# 105848.net
KiCad netlist of a schematic drawn in Altium Designer
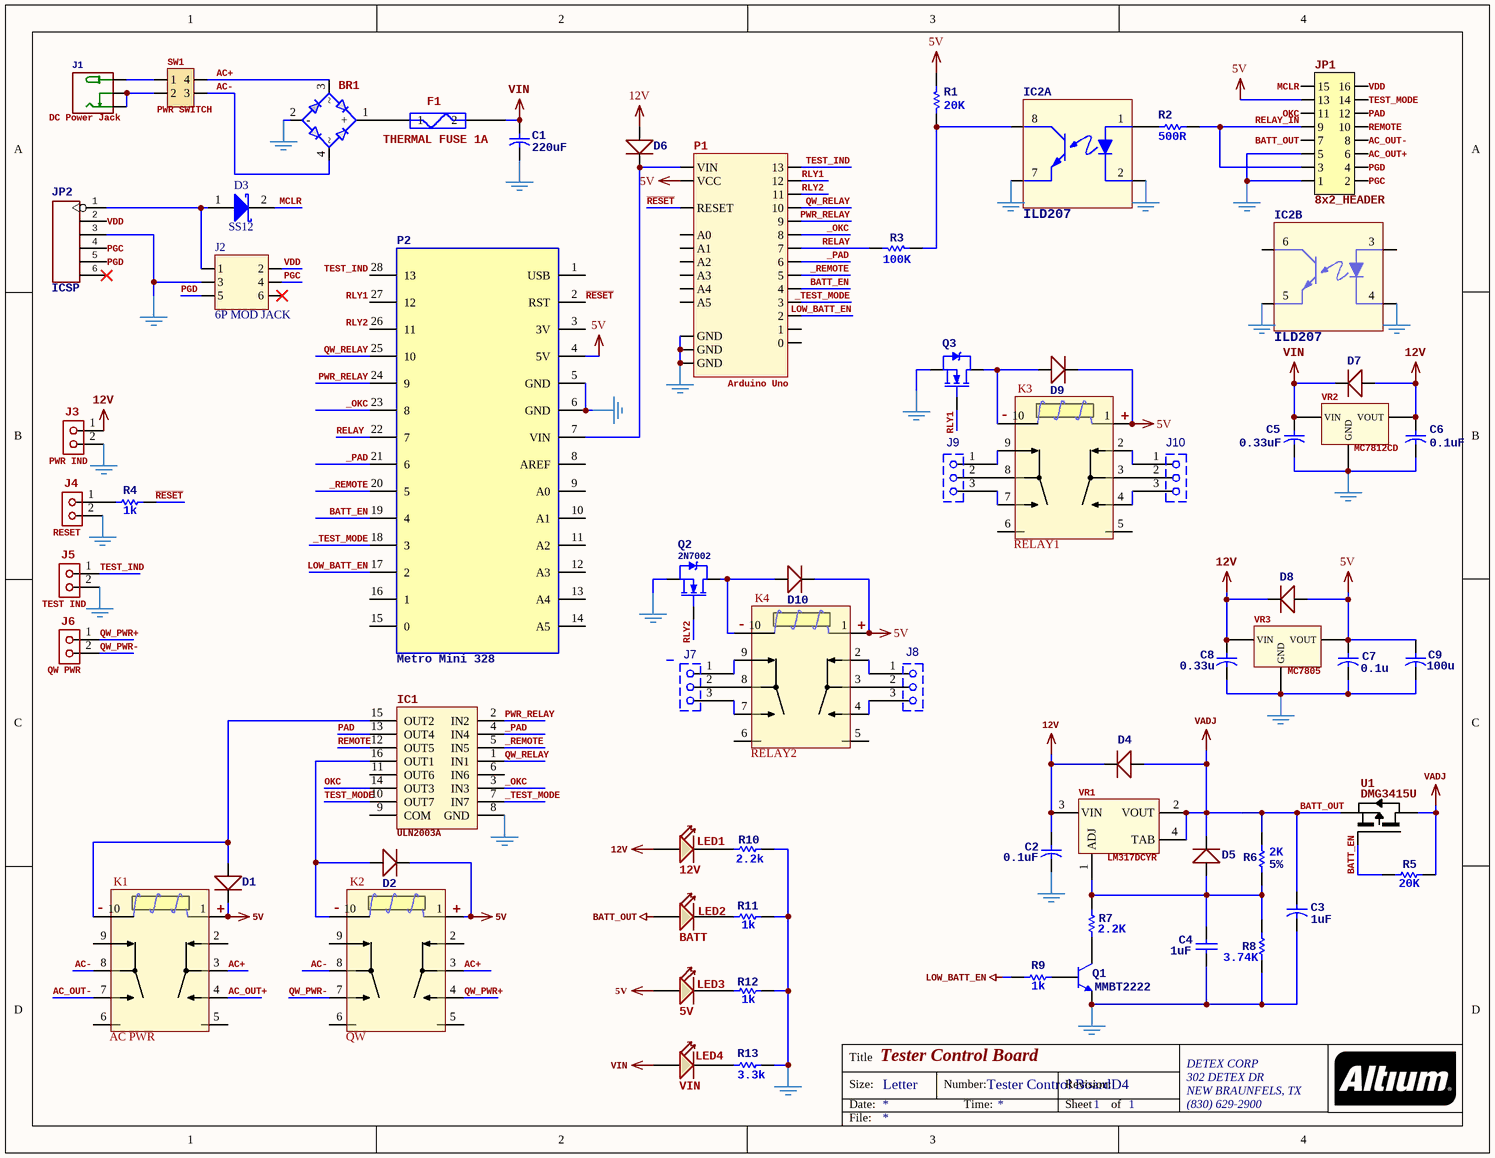
[diagram p0: 105848.SchDoc]

(export (version "E")
  (design (tool "Eeschema 10.0.6"))
  (components
    (comp (ref "BR1")
      (value "BRIDGE - SMT")
      (footprint "BRIDGE_1A_SMT")
      (description "1A SMT Bridge Rectifier")
      (libsource (lib "AltiumIntegratedLibrary") (part "BRIDGE_1A_SMT"))
    )
    (comp (ref "C1")
      (value "220uF")
      (footprint "CAPR5-4X5")
      (description "Capacitor TO - 200 SPACING")
      (fields (field (name "Comment") "Capacitor - Thru-Hole"))
      (libsource (lib "Train2") (part "CAP200"))
    )
    (comp (ref "C2")
      (value "0.1uF")
      (footprint "CAPC1206(3216)110_M")
      (description "1206 Ceramic Capacitor")
      (fields (field (name "Comment") "1206 Capacitor"))
      (libsource (lib "Train2") (part "CAP200"))
    )
    (comp (ref "C3")
      (value "1uF")
      (footprint "CAPC1206(3216)110_M")
      (description "1206 Ceramic Capacitor")
      (fields (field (name "Comment") "1206 Capacitor"))
      (libsource (lib "Train2") (part "CAP200"))
    )
    (comp (ref "C4")
      (value "1uF")
      (footprint "CAPC1206(3216)110_M")
      (description "1206 Ceramic Capacitor")
      (fields (field (name "Comment") "1206 Capacitor"))
      (libsource (lib "Miscellaneous Devices") (part "Cap"))
    )
    (comp (ref "C5")
      (value "0.33uF")
      (footprint "RESC1206(3216)_M")
      (description "1206 Ceramic Capacitor")
      (fields (field (name "Comment") "1206 Capacitor"))
      (libsource (lib "Train2") (part "CAP200"))
    )
    (comp (ref "C6")
      (value "0.1uF")
      (footprint "RESC1206(3216)_M")
      (description "1206 Ceramic Capacitor")
      (fields (field (name "Comment") "1206 Capacitor"))
      (libsource (lib "") (part "CAP200_1"))
    )
    (comp (ref "C7")
      (value "0.1u")
      (footprint "RESC1206(3216)_M")
      (description "1206 Ceramic Capacitor")
      (fields (field (name "Comment") "1206 Capacitor"))
      (libsource (lib "") (part "CAP200_1"))
    )
    (comp (ref "C8")
      (value "0.33u")
      (footprint "RESC1206(3216)_M")
      (description "1206 Ceramic Capacitor")
      (fields (field (name "Comment") "1206 Capacitor"))
      (libsource (lib "") (part "CAP200_1"))
    )
    (comp (ref "C9")
      (value "100u")
      (footprint "CAPR5-4X5")
      (description "Capacitor TO - 200 SPACING")
      (fields (field (name "Comment") "Capacitor - Thru-Hole"))
      (libsource (lib "Train2") (part "CAP200"))
    )
    (comp (ref "D1")
      (value "BAS20")
      (footprint "SOT-23_M")
      (fields (field (name "MPN") "B5819W"))
      (libsource (lib "Seeed-Diode-2016") (part "SMD-DIODE-SCHOTTKY-20V-1A(SOD-123)"))
    )
    (comp (ref "D2")
      (value "BAS20")
      (footprint "SOT-23_M")
      (fields (field (name "MPN") "B5819W"))
      (libsource (lib "Seeed-Diode-2016") (part "SMD-DIODE-SCHOTTKY-20V-1A(SOD-123)"))
    )
    (comp (ref "D3")
      (value "SS12")
      (footprint "SMB_2")
      (description "Schottky Diode, SMD")
      (libsource (lib "Miscellaneous Devices") (part "D Schottky"))
    )
    (comp (ref "D4")
      (value "1N4002")
      (footprint "DO-214AC")
      (description "Diode, SMD")
      (fields (field (name "MPN") "B5819W"))
      (libsource (lib "AltiumIntegratedLibrary") (part "SMD-DIODE-SCHOTTKY-20V-1A(SOD-123)"))
    )
    (comp (ref "D5")
      (value "1N4002")
      (footprint "DO-214AC")
      (description "Diode, SMD")
      (fields (field (name "MPN") "B5819W"))
      (libsource (lib "AltiumIntegratedLibrary") (part "SMD-DIODE-SCHOTTKY-20V-1A(SOD-123)"))
    )
    (comp (ref "D6")
      (value "1N4002")
      (footprint "DO-214AC")
      (description "Diode, SMD")
      (fields (field (name "MPN") "B5819W"))
      (libsource (lib "AltiumIntegratedLibrary") (part "SMD-DIODE-SCHOTTKY-20V-1A(SOD-123)"))
    )
    (comp (ref "D7")
      (value "1N4002")
      (footprint "DO-214AC")
      (description "Diode, SMD")
      (fields (field (name "MPN") "B5819W"))
      (libsource (lib "AltiumIntegratedLibrary") (part "SMD-DIODE-SCHOTTKY-20V-1A(SOD-123)"))
    )
    (comp (ref "D8")
      (value "1N4002")
      (footprint "DO-214AC")
      (description "Diode, SMD")
      (fields (field (name "MPN") "B5819W"))
      (libsource (lib "AltiumIntegratedLibrary") (part "SMD-DIODE-SCHOTTKY-20V-1A(SOD-123)"))
    )
    (comp (ref "D9")
      (value "BAS20")
      (footprint "SOT-23_M")
      (description "Diode, SMD")
      (fields (field (name "MPN") "B5819W"))
      (libsource (lib "AltiumIntegratedLibrary") (part "SMD-DIODE-SCHOTTKY-20V-1A(SOD-123)"))
    )
    (comp (ref "D10")
      (value "BAS20")
      (footprint "SOT-23_M")
      (fields (field (name "MPN") "B5819W"))
      (libsource (lib "AltiumIntegratedLibrary") (part "SMD-DIODE-SCHOTTKY-20V-1A(SOD-123)"))
    )
    (comp (ref "F1")
      (value "THERMAL FUSE 1A")
      (footprint "FUSE_200")
      (description "FUSE_200")
      (libsource (lib "Train2") (part "FUSE_200"))
    )
    (comp (ref "IC1")
      (value "ULN2003A")
      (footprint "SO-16_M")
      (description "ULN2003")
      (libsource (lib "Train2") (part "ULN2003"))
    )
    (comp (ref "IC2")
      (value "ILD207")
      (footprint "SO8_N")
      (description "DUAL OPTO ISOLATOR")
      (fields (field (name "MPN") "ILD207T"))
      (libsource (lib "AltiumIntegratedLibrary") (part "OPTO_DUAL_2"))
    )
    (comp (ref "J1")
      (value "DC Power Jack")
      (footprint "train2:KLD-0202_2")
      (description "DC POWER PLUG")
      (fields (field (name "MPN") "DC-005"))
      (libsource (lib "Seeed-Connector -2016") (part "CONN-POWER-JACK-2.1MM(DC-005)"))
    )
    (comp (ref "J2")
      (value "6P MOD JACK")
      (footprint "TECO-5520470-3_V")
      (description "6 Position Modular Jack Connector")
      (fields (field (name "MANUFACTURER") "Tetco") (field (name "MPN") "TECO-5520470-3_V"))
      (libsource (lib "105848_revD3") (part "Modular Jack 6P"))
    )
    (comp (ref "J3")
      (value "PWR IND")
      (footprint "JMP2")
      (description "JUMPER_2")
      (libsource (lib "105848") (part "JUMPER_2"))
    )
    (comp (ref "J4")
      (value "RESET")
      (footprint "JMP2")
      (description "JUMPER_2")
      (libsource (lib "105848") (part "JUMPER_2"))
    )
    (comp (ref "J5")
      (value "TEST IND")
      (footprint "JMP2")
      (description "JUMPER_2")
      (libsource (lib "105848") (part "JUMPER_2"))
    )
    (comp (ref "J6")
      (value "QW PWR")
      (footprint "JMP2")
      (description "JUMPER_2")
      (libsource (lib "105848") (part "JUMPER_2"))
    )
    (comp (ref "J7")
      (value "JMP_3PIN")
      (footprint "JMP3")
      (libsource (lib "AltiumIntegratedLibrary") (part "JMP_3PIN"))
    )
    (comp (ref "J8")
      (value "JMP_3PIN")
      (footprint "JMP3")
      (libsource (lib "AltiumIntegratedLibrary") (part "JMP_3PIN"))
    )
    (comp (ref "J9")
      (value "JMP_3PIN")
      (footprint "JMP3")
      (libsource (lib "AltiumIntegratedLibrary") (part "JMP_3PIN"))
    )
    (comp (ref "J10")
      (value "JMP_3PIN")
      (footprint "JMP3")
      (libsource (lib "AltiumIntegratedLibrary") (part "JMP_3PIN"))
    )
    (comp (ref "JP1")
      (value "8x2_HEADER")
      (footprint "HDR2X8")
      (description "Ribbon Cable Connection")
      (libsource (lib "105848") (part "15C_2ROW_HEADER"))
    )
    (comp (ref "JP2")
      (value "ICSP")
      (footprint "HDR1X6")
      (description "DIP-BLACK-MALE-HEADER(6P-2.54)")
      (fields (field (name "MPN") "P125-1106A1BS116A1"))
      (libsource (lib "Seeed-Connector -2016") (part "DIP-BLACK-MALE-HEADER(6P-2.54)"))
    )
    (comp (ref "K1")
      (value "AC PWR")
      (footprint "AZ_940")
      (description "AZ850-5")
      (fields (field (name "PART NUMBER") "101671") (field (name "MANUFACTURER") "Zetler"))
      (libsource (lib "105848") (part "Relay_1"))
    )
    (comp (ref "K2")
      (value "QW")
      (footprint "AZ_940")
      (description "AZ850-5")
      (fields (field (name "PART NUMBER") "101671") (field (name "MANUFACTURER") "Zetler"))
      (libsource (lib "105848") (part "Relay_1"))
    )
    (comp (ref "K3")
      (value "RELAY1")
      (footprint "AZ_940")
      (description "AZ850-5")
      (fields (field (name "PART NUMBER") "101671") (field (name "MANUFACTURER") "Zetler"))
      (libsource (lib "105848") (part "Relay_1"))
    )
    (comp (ref "K4")
      (value "RELAY2")
      (footprint "AZ_940")
      (description "AZ850-5")
      (fields (field (name "PART NUMBER") "101671") (field (name "MANUFACTURER") "Zetler"))
      (libsource (lib "105848") (part "Relay_1"))
    )
    (comp (ref "LED1")
      (value "12V")
      (footprint "LED-0805")
      (description "12V Power Indicator")
      (fields (field (name "MPN") "17-215SURC/S530-A2/TR8"))
      (libsource (lib "105848") (part "SMD-LED-CLEAR-RED(0805)"))
    )
    (comp (ref "LED2")
      (value "BATT")
      (footprint "LED-0805")
      (description "Battery Power Indicator")
      (fields (field (name "MPN") "17-215SURC/S530-A2/TR8"))
      (libsource (lib "105848") (part "SMD-LED-CLEAR-RED(0805)"))
    )
    (comp (ref "LED3")
      (value "5V")
      (footprint "LED-0805")
      (description "5V Power Indicator")
      (fields (field (name "MPN") "17-215SURC/S530-A2/TR8"))
      (libsource (lib "105848") (part "SMD-LED-CLEAR-RED(0805)"))
    )
    (comp (ref "LED4")
      (value "VIN")
      (footprint "LED-0805")
      (description "Power Input Indicator")
      (fields (field (name "MPN") "17-215SURC/S530-A2/TR8"))
      (libsource (lib "105848") (part "SMD-LED-CLEAR-RED(0805)"))
    )
    (comp (ref "P1")
      (value "Arduino Uno")
      (footprint "ArduinoUno")
      (fields (field (name "MANUFACTURER") "Arduino.cc"))
      (libsource (lib "105848") (part "Arduino Uno"))
    )
    (comp (ref "P2")
      (value "Metro Mini 328")
      (footprint "Adafruit Metro Mini")
      (description "Adafruit METRO Mini 328 rev A")
      (fields (field (name "MPN") "2590") (field (name "MANUFACTURER") "Adafruit Industries"))
      (libsource (lib "Train2") (part "Metro Mini"))
    )
    (comp (ref "Q1")
      (value "MMBT2222")
      (footprint "SOT-23_M")
      (description "NPN Bipolar Transistor")
      (libsource (lib "Train2") (part "2N3904_SMT"))
    )
    (comp (ref "Q2")
      (value "2N7002")
      (footprint "SOT-23_M")
      (description "N-Channel Enhancement Mode FET")
      (libsource (lib "105848") (part "NMOS-2"))
    )
    (comp (ref "Q3")
      (value "2N7002")
      (footprint "SOT-23_M")
      (description "N-Channel Enhancement Mode FET")
      (libsource (lib "105848") (part "NMOS-2"))
    )
    (comp (ref "R1")
      (value "20K")
      (footprint "RESC1206(3216)_M")
      (description "RESISTOR, SMD, 1206")
      (fields (field (name "TOLERANCE") "5%") (field (name "Comment") "Resistor"))
      (libsource (lib "altium-import") (part "root_3_mirrored_CMP-2003-01077-1_"))
    )
    (comp (ref "R2")
      (value "500R")
      (footprint "RESC1206(3216)_M")
      (description "RESISTOR, SMD, 1206")
      (fields (field (name "TOLERANCE") "5%") (field (name "Comment") "Resistor"))
      (libsource (lib "altium-import") (part "root_2_CMP-2003-01077-1_"))
    )
    (comp (ref "R3")
      (value "100K")
      (footprint "RESC1206(3216)_M")
      (description "RESISTOR, SMD, 1206")
      (fields (field (name "TOLERANCE") "5%") (field (name "Comment") "Resistor"))
      (libsource (lib "altium-import") (part "root_0_mirrored_CMP-2003-01077-1_"))
    )
    (comp (ref "R4")
      (value "1k")
      (footprint "RESC1206(3216)_M")
      (description "RESISTOR, SMD, 1206")
      (fields (field (name "TOLERANCE") "5%") (field (name "Comment") "Resistor"))
      (libsource (lib "altium-import") (part "root_0_CMP-2003-01077-1_"))
    )
    (comp (ref "R5")
      (value "20K")
      (footprint "RESC1206(3216)_M")
      (description "RESISTOR, SMD, 1206")
      (fields (field (name "TOLERANCE") "5%") (field (name "Comment") "Resistor"))
      (libsource (lib "altium-import") (part "root_0_CMP-2003-01077-1_"))
    )
    (comp (ref "R6")
      (value "2K")
      (footprint "RESC1206(3216)_M")
      (description "RESISTOR, SMD, 1206")
      (fields (field (name "TOLERANCE") "5%") (field (name "Comment") "Resistor"))
      (libsource (lib "altium-import") (part "root_3_CMP-2003-01077-1_"))
    )
    (comp (ref "R7")
      (value "2.2K")
      (footprint "RESC1206(3216)_M")
      (description "RESISTOR, SMD, 1206")
      (fields (field (name "TOLERANCE") "5%") (field (name "Comment") "Resistor"))
      (libsource (lib "altium-import") (part "root_3_CMP-2003-01077-1_"))
    )
    (comp (ref "R8")
      (value "3.74K")
      (footprint "RESC1206(3216)_M")
      (description "RESISTOR, SMD, 1206")
      (fields (field (name "TOLERANCE") "5%") (field (name "Comment") "Resistor"))
      (libsource (lib "altium-import") (part "root_3_CMP-2003-01077-1_"))
    )
    (comp (ref "R9")
      (value "1k")
      (footprint "RESC1206(3216)_M")
      (description "RESISTOR, SMD, 1206")
      (fields (field (name "TOLERANCE") "5%") (field (name "Comment") "Resistor"))
      (libsource (lib "altium-import") (part "root_0_CMP-2003-01077-1_"))
    )
    (comp (ref "R10")
      (value "2.2k")
      (footprint "RESC1206(3216)_M")
      (description "RESISTOR, SMD, 1206")
      (fields (field (name "TOLERANCE") "5%") (field (name "Comment") "Resistor"))
      (libsource (lib "altium-import") (part "root_0_CMP-2003-01077-1_"))
    )
    (comp (ref "R11")
      (value "1k")
      (footprint "RESC1206(3216)_M")
      (description "RESISTOR, SMD, 1206")
      (fields (field (name "TOLERANCE") "5%") (field (name "Comment") "Resistor"))
      (libsource (lib "altium-import") (part "root_0_CMP-2003-01077-1_"))
    )
    (comp (ref "R12")
      (value "1k")
      (footprint "RESC1206(3216)_M")
      (description "RESISTOR, SMD, 1206")
      (fields (field (name "TOLERANCE") "5%") (field (name "Comment") "Resistor"))
      (libsource (lib "altium-import") (part "root_0_CMP-2003-01077-1_"))
    )
    (comp (ref "R13")
      (value "3.3k")
      (footprint "RESC1206(3216)_M")
      (description "RESISTOR, SMD, 1206")
      (fields (field (name "TOLERANCE") "5%") (field (name "Comment") "Resistor"))
      (libsource (lib "altium-import") (part "root_0_CMP-2003-01077-1_"))
    )
    (comp (ref "SW1")
      (value "PWR SWITCH")
      (footprint "DPST-4")
      (description "Wire-Board Connection")
      (libsource (lib "105848_revD3") (part "Header 2x2"))
    )
    (comp (ref "U1")
      (value "MOSFET P-CHANNEL")
      (footprint "SOT-23_M")
      (fields (field (name "MPN") "DMG3415U") (field (name "MANUFACTURER") "Diodes, Inc."))
      (libsource (lib "105848") (part "P-CHANNEL MOSFET"))
    )
    (comp (ref "VR1")
      (value "LM317DCYR")
      (footprint "SOT223_M")
      (description "Adjustable SMT Voltage Regulator")
      (fields (field (name "MANUFACTURER") "TI"))
      (libsource (lib "105848") (part "LM317"))
    )
    (comp (ref "VR2")
      (value "MC7812CD")
      (footprint "105848:D2PAK")
      (description "SMT 12V Fixed Output Voltage Regulator")
      (fields (field (name "MPN") "MC7812CD2TG") (field (name "MANUFACTURER") "ON Semi"))
      (libsource (lib "105848") (part "MC7812"))
    )
    (comp (ref "VR3")
      (value "MC7805")
      (footprint "D2PAK")
      (description "SMT 5V Linear Voltage Regulator")
      (fields (field (name "MPN") "MC7805BDTRKG") (field (name "MANUFACTURER") "ON Semi"))
      (libsource (lib "105848") (part "MC7812"))
    )
  )
  (nets
    (net (code "1") (name "/AC+") (class "Default")
      (node (ref "BR1") (pin "3") (pinfunction "~_3") (pintype "passive"))
      (node (ref "K1") (pin "3") (pinfunction "COM_3") (pintype "passive"))
      (node (ref "K2") (pin "3") (pinfunction "COM_3") (pintype "passive"))
      (node (ref "SW1") (pin "4") (pinfunction "4_4") (pintype "passive"))
    )
    (net (code "2") (name "/AC-") (class "Default")
      (node (ref "BR1") (pin "4") (pinfunction "~_4") (pintype "passive"))
      (node (ref "K1") (pin "8") (pinfunction "COM_8") (pintype "passive"))
      (node (ref "K2") (pin "8") (pinfunction "COM_8") (pintype "passive"))
      (node (ref "SW1") (pin "3") (pinfunction "3_3") (pintype "passive"))
    )
    (net (code "3") (name "/AC_OUT+") (class "Default")
      (node (ref "JP1") (pin "6") (pinfunction "6_6") (pintype "passive"))
      (node (ref "K1") (pin "4") (pinfunction "N/O_4") (pintype "passive"))
    )
    (net (code "4") (name "/AC_OUT-") (class "Default")
      (node (ref "JP1") (pin "8") (pinfunction "8_8") (pintype "passive"))
      (node (ref "K1") (pin "7") (pinfunction "N/O_7") (pintype "passive"))
    )
    (net (code "5") (name "/BATT_EN") (class "Default")
      (node (ref "P1") (pin "4") (pinfunction "4_4") (pintype "passive"))
      (node (ref "P2") (pin "19") (pinfunction "4_19") (pintype "passive"))
      (node (ref "R5") (pin "1") (pinfunction "1_1") (pintype "passive"))
      (node (ref "U1") (pin "1") (pinfunction "1_1") (pintype "passive"))
    )
    (net (code "6") (name "/MCLR") (class "Default")
      (node (ref "D3") (pin "2") (pinfunction "K_2") (pintype "passive"))
      (node (ref "JP1") (pin "15") (pinfunction "15_15") (pintype "passive"))
    )
    (net (code "7") (name "/OKC") (class "Default")
      (node (ref "IC1") (pin "14") (pinfunction "OUT3_14") (pintype "passive"))
      (node (ref "JP1") (pin "11") (pinfunction "11_11") (pintype "passive"))
    )
    (net (code "8") (name "/PAD") (class "Default")
      (node (ref "IC1") (pin "13") (pinfunction "OUT4_13") (pintype "passive"))
      (node (ref "JP1") (pin "12") (pinfunction "12_12") (pintype "passive"))
    )
    (net (code "9") (name "/PGC") (class "Default")
      (node (ref "J2") (pin "4") (pinfunction "4_4") (pintype "passive"))
      (node (ref "JP1") (pin "2") (pinfunction "2_2") (pintype "passive"))
      (node (ref "JP2") (pin "4") (pinfunction "4_4") (pintype "passive"))
    )
    (net (code "10") (name "/PGD") (class "Default")
      (node (ref "J2") (pin "5") (pinfunction "5_5") (pintype "passive"))
      (node (ref "JP1") (pin "4") (pinfunction "4_4") (pintype "passive"))
      (node (ref "JP2") (pin "5") (pinfunction "5_5") (pintype "passive"))
    )
    (net (code "11") (name "/PWR_RELAY") (class "Default")
      (node (ref "IC1") (pin "2") (pinfunction "IN2_2") (pintype "passive"))
      (node (ref "P1") (pin "9") (pinfunction "9_9") (pintype "passive"))
      (node (ref "P2") (pin "24") (pinfunction "9_24") (pintype "passive"))
    )
    (net (code "12") (name "/QW_PWR+") (class "Default")
      (node (ref "J6") (pin "1") (pinfunction "1_1") (pintype "passive"))
      (node (ref "K2") (pin "4") (pinfunction "N/O_4") (pintype "passive"))
    )
    (net (code "13") (name "/QW_PWR-") (class "Default")
      (node (ref "J6") (pin "2") (pinfunction "2_2") (pintype "passive"))
      (node (ref "K2") (pin "7") (pinfunction "N/O_7") (pintype "passive"))
    )
    (net (code "14") (name "/QW_RELAY") (class "Default")
      (node (ref "IC1") (pin "1") (pinfunction "IN1_1") (pintype "passive"))
      (node (ref "P1") (pin "10") (pinfunction "10_10") (pintype "passive"))
      (node (ref "P2") (pin "25") (pinfunction "10_25") (pintype "passive"))
    )
    (net (code "15") (name "/RELAY") (class "Default")
      (node (ref "P1") (pin "7") (pinfunction "7_7") (pintype "passive"))
      (node (ref "P2") (pin "22") (pinfunction "7_22") (pintype "passive"))
      (node (ref "R3") (pin "2") (pinfunction "2_2") (pintype "passive"))
    )
    (net (code "16") (name "/RELAY_IN") (class "Default")
      (node (ref "JP1") (pin "3") (pinfunction "3_3") (pintype "passive"))
      (node (ref "JP1") (pin "9") (pinfunction "9_9") (pintype "passive"))
      (node (ref "R2") (pin "1") (pinfunction "1_1") (pintype "passive"))
    )
    (net (code "17") (name "/REMOTE") (class "Default")
      (node (ref "IC1") (pin "12") (pinfunction "OUT5_12") (pintype "passive"))
      (node (ref "JP1") (pin "10") (pinfunction "10_10") (pintype "passive"))
    )
    (net (code "18") (name "/RLY1") (class "Default")
      (node (ref "P1") (pin "12") (pinfunction "12_12") (pintype "passive"))
      (node (ref "P2") (pin "27") (pinfunction "12_27") (pintype "passive"))
      (node (ref "Q3") (pin "1") (pinfunction "G_1") (pintype "passive"))
    )
    (net (code "19") (name "/RLY2") (class "Default")
      (node (ref "P1") (pin "11") (pinfunction "11_11") (pintype "passive"))
      (node (ref "P2") (pin "26") (pinfunction "11_26") (pintype "passive"))
      (node (ref "Q2") (pin "1") (pinfunction "G_1") (pintype "passive"))
    )
    (net (code "20") (name "/TEST_IND") (class "Default")
      (node (ref "J5") (pin "1") (pinfunction "1_1") (pintype "passive"))
      (node (ref "P1") (pin "13") (pinfunction "13_13") (pintype "passive"))
      (node (ref "P2") (pin "28") (pinfunction "13_28") (pintype "passive"))
    )
    (net (code "21") (name "/TEST_MODE") (class "Default")
      (node (ref "IC1") (pin "10") (pinfunction "OUT7_10") (pintype "passive"))
      (node (ref "JP1") (pin "14") (pinfunction "14_14") (pintype "passive"))
    )
    (net (code "22") (name "/VDD") (class "Default")
      (node (ref "J2") (pin "2") (pinfunction "2_2") (pintype "passive"))
      (node (ref "JP1") (pin "16") (pinfunction "16_16") (pintype "passive"))
      (node (ref "JP2") (pin "2") (pinfunction "2_2") (pintype "passive"))
    )
    (net (code "23") (name "/_OKC") (class "Default")
      (node (ref "IC1") (pin "3") (pinfunction "IN3_3") (pintype "passive"))
      (node (ref "P1") (pin "8") (pinfunction "8_8") (pintype "passive"))
      (node (ref "P2") (pin "23") (pinfunction "8_23") (pintype "passive"))
    )
    (net (code "24") (name "/_PAD") (class "Default")
      (node (ref "IC1") (pin "4") (pinfunction "IN4_4") (pintype "passive"))
      (node (ref "P1") (pin "6") (pinfunction "6_6") (pintype "passive"))
      (node (ref "P2") (pin "21") (pinfunction "6_21") (pintype "passive"))
    )
    (net (code "25") (name "/_REMOTE") (class "Default")
      (node (ref "IC1") (pin "5") (pinfunction "IN5_5") (pintype "passive"))
      (node (ref "P1") (pin "5") (pinfunction "5_5") (pintype "passive"))
      (node (ref "P2") (pin "20") (pinfunction "5_20") (pintype "passive"))
    )
    (net (code "26") (name "/_TEST_MODE") (class "Default")
      (node (ref "IC1") (pin "7") (pinfunction "IN7_7") (pintype "passive"))
      (node (ref "P1") (pin "3") (pinfunction "3_3") (pintype "passive"))
      (node (ref "P2") (pin "18") (pinfunction "3_18") (pintype "passive"))
    )
    (net (code "27") (name "/~{RESET}") (class "Default")
      (node (ref "P1") (pin "RESET") (pinfunction "RESET_RESET") (pintype "passive"))
      (node (ref "P2") (pin "2") (pinfunction "RST_2") (pintype "passive"))
      (node (ref "R4") (pin "2") (pinfunction "2_2") (pintype "passive"))
    )
    (net (code "28") (name "5V") (class "Default")
      (node (ref "C7") (pin "1") (pinfunction "1_1") (pintype "passive"))
      (node (ref "C9") (pin "1") (pinfunction "1_1") (pintype "passive"))
      (node (ref "D1") (pin "-") (pinfunction "-_-") (pintype "passive"))
      (node (ref "D10") (pin "-") (pinfunction "-_-") (pintype "passive"))
      (node (ref "D2") (pin "-") (pinfunction "-_-") (pintype "passive"))
      (node (ref "D8") (pin "+") (pinfunction "+_+") (pintype "passive"))
      (node (ref "D9") (pin "-") (pinfunction "-_-") (pintype "passive"))
      (node (ref "JP1") (pin "13") (pinfunction "13_13") (pintype "passive"))
      (node (ref "K1") (pin "1") (pinfunction "V+_1") (pintype "passive"))
      (node (ref "K2") (pin "1") (pinfunction "V+_1") (pintype "passive"))
      (node (ref "K3") (pin "1") (pinfunction "V+_1") (pintype "passive"))
      (node (ref "K4") (pin "1") (pinfunction "V+_1") (pintype "passive"))
      (node (ref "LED3") (pin "+") (pinfunction "+_+") (pintype "passive"))
      (node (ref "P1") (pin "VCC") (pinfunction "VCC_VCC") (pintype "passive"))
      (node (ref "P2") (pin "4") (pinfunction "5V_4") (pintype "passive"))
      (node (ref "R1") (pin "1") (pinfunction "1_1") (pintype "passive"))
      (node (ref "VR3") (pin "3") (pinfunction "VOUT_3") (pintype "passive"))
    )
    (net (code "29") (name "12V") (class "Default")
      (node (ref "C2") (pin "1") (pinfunction "1_1") (pintype "passive"))
      (node (ref "C6") (pin "1") (pinfunction "1_1") (pintype "passive"))
      (node (ref "C8") (pin "1") (pinfunction "1_1") (pintype "passive"))
      (node (ref "D4") (pin "-") (pinfunction "-_-") (pintype "passive"))
      (node (ref "D6") (pin "+") (pinfunction "+_+") (pintype "passive"))
      (node (ref "D7") (pin "+") (pinfunction "+_+") (pintype "passive"))
      (node (ref "D8") (pin "-") (pinfunction "-_-") (pintype "passive"))
      (node (ref "J3") (pin "1") (pinfunction "1_1") (pintype "passive"))
      (node (ref "LED1") (pin "+") (pinfunction "+_+") (pintype "passive"))
      (node (ref "VR1") (pin "3") (pinfunction "VIN_3") (pintype "passive"))
      (node (ref "VR2") (pin "3") (pinfunction "VOUT_3") (pintype "passive"))
      (node (ref "VR3") (pin "1") (pinfunction "VIN_1") (pintype "passive"))
    )
    (net (code "30") (name "BATT_OUT") (class "Default")
      (node (ref "C3") (pin "1") (pinfunction "1_1") (pintype "passive"))
      (node (ref "D4") (pin "+") (pinfunction "+_+") (pintype "passive"))
      (node (ref "D5") (pin "-") (pinfunction "-_-") (pintype "passive"))
      (node (ref "JP1") (pin "7") (pinfunction "7_7") (pintype "passive"))
      (node (ref "LED2") (pin "+") (pinfunction "+_+") (pintype "passive"))
      (node (ref "R5") (pin "2") (pinfunction "2_2") (pintype "passive"))
      (node (ref "R6") (pin "1") (pinfunction "1_1") (pintype "passive"))
      (node (ref "U1") (pin "2") (pinfunction "2_2") (pintype "passive"))
      (node (ref "U1") (pin "3") (pinfunction "3_3") (pintype "passive"))
      (node (ref "VR1") (pin "2") (pinfunction "VOUT_2") (pintype "passive"))
      (node (ref "VR1") (pin "4") (pinfunction "TAB_4") (pintype "passive"))
    )
    (net (code "31") (name "GND") (class "Default")
      (node (ref "BR1") (pin "2") (pinfunction "-_2") (pintype "passive"))
      (node (ref "C1") (pin "2") (pinfunction "2_2") (pintype "passive"))
      (node (ref "C2") (pin "2") (pinfunction "2_2") (pintype "passive"))
      (node (ref "C3") (pin "2") (pinfunction "2_2") (pintype "passive"))
      (node (ref "C4") (pin "1") (pinfunction "1_1") (pintype "passive"))
      (node (ref "C5") (pin "2") (pinfunction "2_2") (pintype "passive"))
      (node (ref "C6") (pin "2") (pinfunction "2_2") (pintype "passive"))
      (node (ref "C7") (pin "2") (pinfunction "2_2") (pintype "passive"))
      (node (ref "C8") (pin "2") (pinfunction "2_2") (pintype "passive"))
      (node (ref "C9") (pin "2") (pinfunction "2_2") (pintype "passive"))
      (node (ref "IC1") (pin "8") (pinfunction "GND_8") (pintype "passive"))
      (node (ref "IC2") (pin "2") (pinfunction "C1_2") (pintype "passive"))
      (node (ref "IC2") (pin "4") (pinfunction "C2_4") (pintype "passive"))
      (node (ref "IC2") (pin "5") (pinfunction "E2_5") (pintype "passive"))
      (node (ref "IC2") (pin "7") (pinfunction "E1_7") (pintype "passive"))
      (node (ref "J2") (pin "3") (pinfunction "3_3") (pintype "passive"))
      (node (ref "J3") (pin "2") (pinfunction "2_2") (pintype "passive"))
      (node (ref "J4") (pin "2") (pinfunction "2_2") (pintype "passive"))
      (node (ref "J5") (pin "2") (pinfunction "2_2") (pintype "passive"))
      (node (ref "JP1") (pin "1") (pinfunction "1_1") (pintype "passive"))
      (node (ref "JP1") (pin "5") (pinfunction "5_5") (pintype "passive"))
      (node (ref "JP2") (pin "3") (pinfunction "3_3") (pintype "passive"))
      (node (ref "P1") (pin "GND") (pinfunction "GND_GND") (pintype "passive"))
      (node (ref "P1") (pin "GND1") (pinfunction "GND_GND1") (pintype "passive"))
      (node (ref "P1") (pin "GND2") (pinfunction "GND_GND2") (pintype "passive"))
      (node (ref "P2") (pin "5") (pinfunction "GND_5") (pintype "passive"))
      (node (ref "P2") (pin "6") (pinfunction "GND_6") (pintype "passive"))
      (node (ref "Q1") (pin "2") (pinfunction "2_2") (pintype "passive"))
      (node (ref "Q2") (pin "2") (pinfunction "S_2") (pintype "passive"))
      (node (ref "Q3") (pin "2") (pinfunction "S_2") (pintype "passive"))
      (node (ref "R10") (pin "2") (pinfunction "2_2") (pintype "passive"))
      (node (ref "R11") (pin "2") (pinfunction "2_2") (pintype "passive"))
      (node (ref "R12") (pin "2") (pinfunction "2_2") (pintype "passive"))
      (node (ref "R13") (pin "2") (pinfunction "2_2") (pintype "passive"))
      (node (ref "R8") (pin "2") (pinfunction "2_2") (pintype "passive"))
      (node (ref "VR2") (pin "2") (pinfunction "GND_2") (pintype "power_in"))
      (node (ref "VR3") (pin "2") (pinfunction "GND_2") (pintype "power_in"))
    )
    (net (code "32") (name "LOW_BATT_EN") (class "Default")
      (node (ref "P1") (pin "2") (pinfunction "2_2") (pintype "passive"))
      (node (ref "P2") (pin "17") (pinfunction "2_17") (pintype "passive"))
      (node (ref "R9") (pin "1") (pinfunction "1_1") (pintype "passive"))
    )
    (net (code "33") (name "Net-(BR1-+)") (class "Default")
      (node (ref "BR1") (pin "1") (pinfunction "+_1") (pintype "passive"))
      (node (ref "F1") (pin "1") (pinfunction "1_1") (pintype "passive"))
    )
    (net (code "34") (name "Net-(D3-A)") (class "Default")
      (node (ref "D3") (pin "1") (pinfunction "A_1") (pintype "passive"))
      (node (ref "J2") (pin "1") (pinfunction "1_1") (pintype "passive"))
      (node (ref "JP2") (pin "1") (pinfunction "1_1") (pintype "passive"))
    )
    (net (code "35") (name "Net-(IC1-OUT1)") (class "Default")
      (node (ref "D2") (pin "+") (pinfunction "+_+") (pintype "passive"))
      (node (ref "IC1") (pin "16") (pinfunction "OUT1_16") (pintype "passive"))
      (node (ref "K2") (pin "10") (pinfunction "V-_10") (pintype "passive"))
    )
    (net (code "36") (name "Net-(IC1-OUT2)") (class "Default")
      (node (ref "D1") (pin "+") (pinfunction "+_+") (pintype "passive"))
      (node (ref "IC1") (pin "15") (pinfunction "OUT2_15") (pintype "passive"))
      (node (ref "K1") (pin "10") (pinfunction "V-_10") (pintype "passive"))
    )
    (net (code "37") (name "Net-(IC2A-A1)") (class "Default")
      (node (ref "IC2") (pin "1") (pinfunction "A1_1") (pintype "passive"))
      (node (ref "R2") (pin "2") (pinfunction "2_2") (pintype "passive"))
    )
    (net (code "38") (name "Net-(IC2A-COL1)") (class "Default")
      (node (ref "IC2") (pin "8") (pinfunction "COL1_8") (pintype "passive"))
      (node (ref "R1") (pin "2") (pinfunction "2_2") (pintype "passive"))
      (node (ref "R3") (pin "1") (pinfunction "1_1") (pintype "passive"))
    )
    (net (code "39") (name "Net-(J1--)") (class "Default")
      (node (ref "J1") (pin "-1") (pinfunction "-_-1") (pintype "passive"))
      (node (ref "J1") (pin "-2") (pinfunction "CDN_-2") (pintype "passive"))
      (node (ref "SW1") (pin "2") (pinfunction "2_2") (pintype "passive"))
    )
    (net (code "40") (name "Net-(J1-Pad+)") (class "Default")
      (node (ref "J1") (pin "+") (pinfunction "+_+") (pintype "passive"))
      (node (ref "SW1") (pin "1") (pinfunction "1_1") (pintype "passive"))
    )
    (net (code "41") (name "Net-(J4-Pad1)") (class "Default")
      (node (ref "J4") (pin "1") (pinfunction "1_1") (pintype "passive"))
      (node (ref "R4") (pin "1") (pinfunction "1_1") (pintype "passive"))
    )
    (net (code "42") (name "Net-(J7-16)") (class "Default")
      (node (ref "J7") (pin "1") (pinfunction "16_1") (pintype "passive"))
      (node (ref "K4") (pin "9") (pinfunction "N/C_9") (pintype "passive"))
    )
    (net (code "43") (name "Net-(J7-32)") (class "Default")
      (node (ref "J7") (pin "3") (pinfunction "32_3") (pintype "passive"))
      (node (ref "K4") (pin "7") (pinfunction "N/O_7") (pintype "passive"))
    )
    (net (code "44") (name "Net-(J7-Pad2)") (class "Default")
      (node (ref "J7") (pin "2") (pintype "passive"))
      (node (ref "K4") (pin "8") (pinfunction "COM_8") (pintype "passive"))
    )
    (net (code "45") (name "Net-(J8-16)") (class "Default")
      (node (ref "J8") (pin "1") (pinfunction "16_1") (pintype "passive"))
      (node (ref "K4") (pin "2") (pinfunction "N/C_2") (pintype "passive"))
    )
    (net (code "46") (name "Net-(J8-32)") (class "Default")
      (node (ref "J8") (pin "3") (pinfunction "32_3") (pintype "passive"))
      (node (ref "K4") (pin "4") (pinfunction "N/O_4") (pintype "passive"))
    )
    (net (code "47") (name "Net-(J8-Pad2)") (class "Default")
      (node (ref "J8") (pin "2") (pintype "passive"))
      (node (ref "K4") (pin "3") (pinfunction "COM_3") (pintype "passive"))
    )
    (net (code "48") (name "Net-(J9-16)") (class "Default")
      (node (ref "J9") (pin "1") (pinfunction "16_1") (pintype "passive"))
      (node (ref "K3") (pin "9") (pinfunction "N/C_9") (pintype "passive"))
    )
    (net (code "49") (name "Net-(J9-32)") (class "Default")
      (node (ref "J9") (pin "3") (pinfunction "32_3") (pintype "passive"))
      (node (ref "K3") (pin "7") (pinfunction "N/O_7") (pintype "passive"))
    )
    (net (code "50") (name "Net-(J9-Pad2)") (class "Default")
      (node (ref "J9") (pin "2") (pintype "passive"))
      (node (ref "K3") (pin "8") (pinfunction "COM_8") (pintype "passive"))
    )
    (net (code "51") (name "Net-(J10-16)") (class "Default")
      (node (ref "J10") (pin "1") (pinfunction "16_1") (pintype "passive"))
      (node (ref "K3") (pin "2") (pinfunction "N/C_2") (pintype "passive"))
    )
    (net (code "52") (name "Net-(J10-32)") (class "Default")
      (node (ref "J10") (pin "3") (pinfunction "32_3") (pintype "passive"))
      (node (ref "K3") (pin "4") (pinfunction "N/O_4") (pintype "passive"))
    )
    (net (code "53") (name "Net-(J10-Pad2)") (class "Default")
      (node (ref "J10") (pin "2") (pintype "passive"))
      (node (ref "K3") (pin "3") (pinfunction "COM_3") (pintype "passive"))
    )
    (net (code "54") (name "Net-(K3-V-)") (class "Default")
      (node (ref "D9") (pin "+") (pinfunction "+_+") (pintype "passive"))
      (node (ref "K3") (pin "10") (pinfunction "V-_10") (pintype "passive"))
      (node (ref "Q3") (pin "3") (pinfunction "D_3") (pintype "passive"))
    )
    (net (code "55") (name "Net-(K4-V-)") (class "Default")
      (node (ref "D10") (pin "+") (pinfunction "+_+") (pintype "passive"))
      (node (ref "K4") (pin "10") (pinfunction "V-_10") (pintype "passive"))
      (node (ref "Q2") (pin "3") (pinfunction "D_3") (pintype "passive"))
    )
    (net (code "56") (name "Net-(LED1-Pad-)") (class "Default")
      (node (ref "LED1") (pin "-") (pinfunction "-_-") (pintype "passive"))
      (node (ref "R10") (pin "1") (pinfunction "1_1") (pintype "passive"))
    )
    (net (code "57") (name "Net-(LED2-Pad-)") (class "Default")
      (node (ref "LED2") (pin "-") (pinfunction "-_-") (pintype "passive"))
      (node (ref "R11") (pin "1") (pinfunction "1_1") (pintype "passive"))
    )
    (net (code "58") (name "Net-(LED3-Pad-)") (class "Default")
      (node (ref "LED3") (pin "-") (pinfunction "-_-") (pintype "passive"))
      (node (ref "R12") (pin "1") (pinfunction "1_1") (pintype "passive"))
    )
    (net (code "59") (name "Net-(LED4-Pad-)") (class "Default")
      (node (ref "LED4") (pin "-") (pinfunction "-_-") (pintype "passive"))
      (node (ref "R13") (pin "1") (pinfunction "1_1") (pintype "passive"))
    )
    (net (code "60") (name "Net-(P2-VIN)") (class "Default")
      (node (ref "D6") (pin "-") (pinfunction "-_-") (pintype "passive"))
      (node (ref "P1") (pin "VIN") (pinfunction "VIN_VIN") (pintype "passive"))
      (node (ref "P2") (pin "7") (pinfunction "VIN_7") (pintype "passive"))
    )
    (net (code "61") (name "Net-(Q1-Pad1)") (class "Default")
      (node (ref "Q1") (pin "1") (pinfunction "1_1") (pintype "passive"))
      (node (ref "R9") (pin "2") (pinfunction "2_2") (pintype "passive"))
    )
    (net (code "62") (name "Net-(Q1-Pad3)") (class "Default")
      (node (ref "Q1") (pin "3") (pinfunction "3_3") (pintype "passive"))
      (node (ref "R7") (pin "2") (pinfunction "2_2") (pintype "passive"))
    )
    (net (code "63") (name "Net-(VR1-ADJ)") (class "Default")
      (node (ref "C4") (pin "2") (pinfunction "2_2") (pintype "passive"))
      (node (ref "D5") (pin "+") (pinfunction "+_+") (pintype "passive"))
      (node (ref "R6") (pin "2") (pinfunction "2_2") (pintype "passive"))
      (node (ref "R7") (pin "1") (pinfunction "1_1") (pintype "passive"))
      (node (ref "R8") (pin "1") (pinfunction "1_1") (pintype "passive"))
      (node (ref "VR1") (pin "1") (pinfunction "ADJ_1") (pintype "passive"))
    )
    (net (code "64") (name "VIN") (class "Default")
      (node (ref "C1") (pin "1") (pinfunction "1_1") (pintype "passive"))
      (node (ref "C5") (pin "1") (pinfunction "1_1") (pintype "passive"))
      (node (ref "D7") (pin "-") (pinfunction "-_-") (pintype "passive"))
      (node (ref "F1") (pin "2") (pinfunction "2_2") (pintype "passive"))
      (node (ref "LED4") (pin "+") (pinfunction "+_+") (pintype "passive"))
      (node (ref "VR2") (pin "1") (pinfunction "VIN_1") (pintype "passive"))
    )
    (net (code "65") (name "unconnected-(IC1-COM-Pad9)") (class "Default")
      (node (ref "IC1") (pin "9") (pinfunction "COM_9") (pintype "passive"))
    )
    (net (code "66") (name "unconnected-(IC1-IN6-Pad6)") (class "Default")
      (node (ref "IC1") (pin "6") (pinfunction "IN6_6") (pintype "passive"))
    )
    (net (code "67") (name "unconnected-(IC1-OUT6-Pad11)") (class "Default")
      (node (ref "IC1") (pin "11") (pinfunction "OUT6_11") (pintype "passive"))
    )
    (net (code "68") (name "unconnected-(IC2B-A2-Pad3)") (class "Default")
      (node (ref "IC2") (pin "3") (pinfunction "A2_3") (pintype "passive"))
    )
    (net (code "69") (name "unconnected-(IC2B-COL2-Pad6)") (class "Default")
      (node (ref "IC2") (pin "6") (pinfunction "COL2_6") (pintype "passive"))
    )
    (net (code "70") (name "unconnected-(J2-Pad6)") (class "Default")
      (node (ref "J2") (pin "6") (pinfunction "6_6") (pintype "passive+no_connect"))
    )
    (net (code "71") (name "unconnected-(JP2-Pad6)") (class "Default")
      (node (ref "JP2") (pin "6") (pinfunction "6_6") (pintype "passive+no_connect"))
    )
    (net (code "72") (name "unconnected-(K1-N{slash}C-Pad2)") (class "Default")
      (node (ref "K1") (pin "2") (pinfunction "N/C_2") (pintype "passive"))
    )
    (net (code "73") (name "unconnected-(K1-N{slash}C-Pad9)") (class "Default")
      (node (ref "K1") (pin "9") (pinfunction "N/C_9") (pintype "passive"))
    )
    (net (code "74") (name "unconnected-(K1-Pad5)") (class "Default")
      (node (ref "K1") (pin "5") (pintype "passive"))
    )
    (net (code "75") (name "unconnected-(K1-Pad6)") (class "Default")
      (node (ref "K1") (pin "6") (pintype "passive"))
    )
    (net (code "76") (name "unconnected-(K2-N{slash}C-Pad2)") (class "Default")
      (node (ref "K2") (pin "2") (pinfunction "N/C_2") (pintype "passive"))
    )
    (net (code "77") (name "unconnected-(K2-N{slash}C-Pad9)") (class "Default")
      (node (ref "K2") (pin "9") (pinfunction "N/C_9") (pintype "passive"))
    )
    (net (code "78") (name "unconnected-(K2-Pad5)") (class "Default")
      (node (ref "K2") (pin "5") (pintype "passive"))
    )
    (net (code "79") (name "unconnected-(K2-Pad6)") (class "Default")
      (node (ref "K2") (pin "6") (pintype "passive"))
    )
    (net (code "80") (name "unconnected-(K3-Pad5)") (class "Default")
      (node (ref "K3") (pin "5") (pintype "passive"))
    )
    (net (code "81") (name "unconnected-(K3-Pad6)") (class "Default")
      (node (ref "K3") (pin "6") (pintype "passive"))
    )
    (net (code "82") (name "unconnected-(K4-Pad5)") (class "Default")
      (node (ref "K4") (pin "5") (pintype "passive"))
    )
    (net (code "83") (name "unconnected-(K4-Pad6)") (class "Default")
      (node (ref "K4") (pin "6") (pintype "passive"))
    )
    (net (code "84") (name "unconnected-(P1-Pad0)") (class "Default")
      (node (ref "P1") (pin "0") (pinfunction "0_0") (pintype "passive"))
    )
    (net (code "85") (name "unconnected-(P1-Pad1)") (class "Default")
      (node (ref "P1") (pin "1") (pinfunction "1_1") (pintype "passive"))
    )
    (net (code "86") (name "unconnected-(P1-PadA0)") (class "Default")
      (node (ref "P1") (pin "A0") (pinfunction "A0_A0") (pintype "passive"))
    )
    (net (code "87") (name "unconnected-(P1-PadA1)") (class "Default")
      (node (ref "P1") (pin "A1") (pinfunction "A1_A1") (pintype "passive"))
    )
    (net (code "88") (name "unconnected-(P1-PadA2)") (class "Default")
      (node (ref "P1") (pin "A2") (pinfunction "A2_A2") (pintype "passive"))
    )
    (net (code "89") (name "unconnected-(P1-PadA3)") (class "Default")
      (node (ref "P1") (pin "A3") (pinfunction "A3_A3") (pintype "passive"))
    )
    (net (code "90") (name "unconnected-(P1-PadA4)") (class "Default")
      (node (ref "P1") (pin "A4") (pinfunction "A4_A4") (pintype "passive"))
    )
    (net (code "91") (name "unconnected-(P1-PadA5)") (class "Default")
      (node (ref "P1") (pin "A5") (pinfunction "A5_A5") (pintype "passive"))
    )
    (net (code "92") (name "unconnected-(P2-0-Pad15)") (class "Default")
      (node (ref "P2") (pin "15") (pinfunction "0_15") (pintype "passive"))
    )
    (net (code "93") (name "unconnected-(P2-1-Pad16)") (class "Default")
      (node (ref "P2") (pin "16") (pinfunction "1_16") (pintype "passive"))
    )
    (net (code "94") (name "unconnected-(P2-3V-Pad3)") (class "Default")
      (node (ref "P2") (pin "3") (pinfunction "3V_3") (pintype "passive"))
    )
    (net (code "95") (name "unconnected-(P2-A0-Pad9)") (class "Default")
      (node (ref "P2") (pin "9") (pinfunction "A0_9") (pintype "passive"))
    )
    (net (code "96") (name "unconnected-(P2-A1-Pad10)") (class "Default")
      (node (ref "P2") (pin "10") (pinfunction "A1_10") (pintype "passive"))
    )
    (net (code "97") (name "unconnected-(P2-A2-Pad11)") (class "Default")
      (node (ref "P2") (pin "11") (pinfunction "A2_11") (pintype "passive"))
    )
    (net (code "98") (name "unconnected-(P2-A3-Pad12)") (class "Default")
      (node (ref "P2") (pin "12") (pinfunction "A3_12") (pintype "passive"))
    )
    (net (code "99") (name "unconnected-(P2-A4-Pad13)") (class "Default")
      (node (ref "P2") (pin "13") (pinfunction "A4_13") (pintype "passive"))
    )
    (net (code "100") (name "unconnected-(P2-A5-Pad14)") (class "Default")
      (node (ref "P2") (pin "14") (pinfunction "A5_14") (pintype "passive"))
    )
    (net (code "101") (name "unconnected-(P2-AREF-Pad8)") (class "Default")
      (node (ref "P2") (pin "8") (pinfunction "AREF_8") (pintype "passive"))
    )
    (net (code "102") (name "unconnected-(P2-USB-Pad1)") (class "Default")
      (node (ref "P2") (pin "1") (pinfunction "USB_1") (pintype "passive"))
    )
  )
)
